# fakealarm.net
KiCad netlist of a schematic drawn in EAGLE
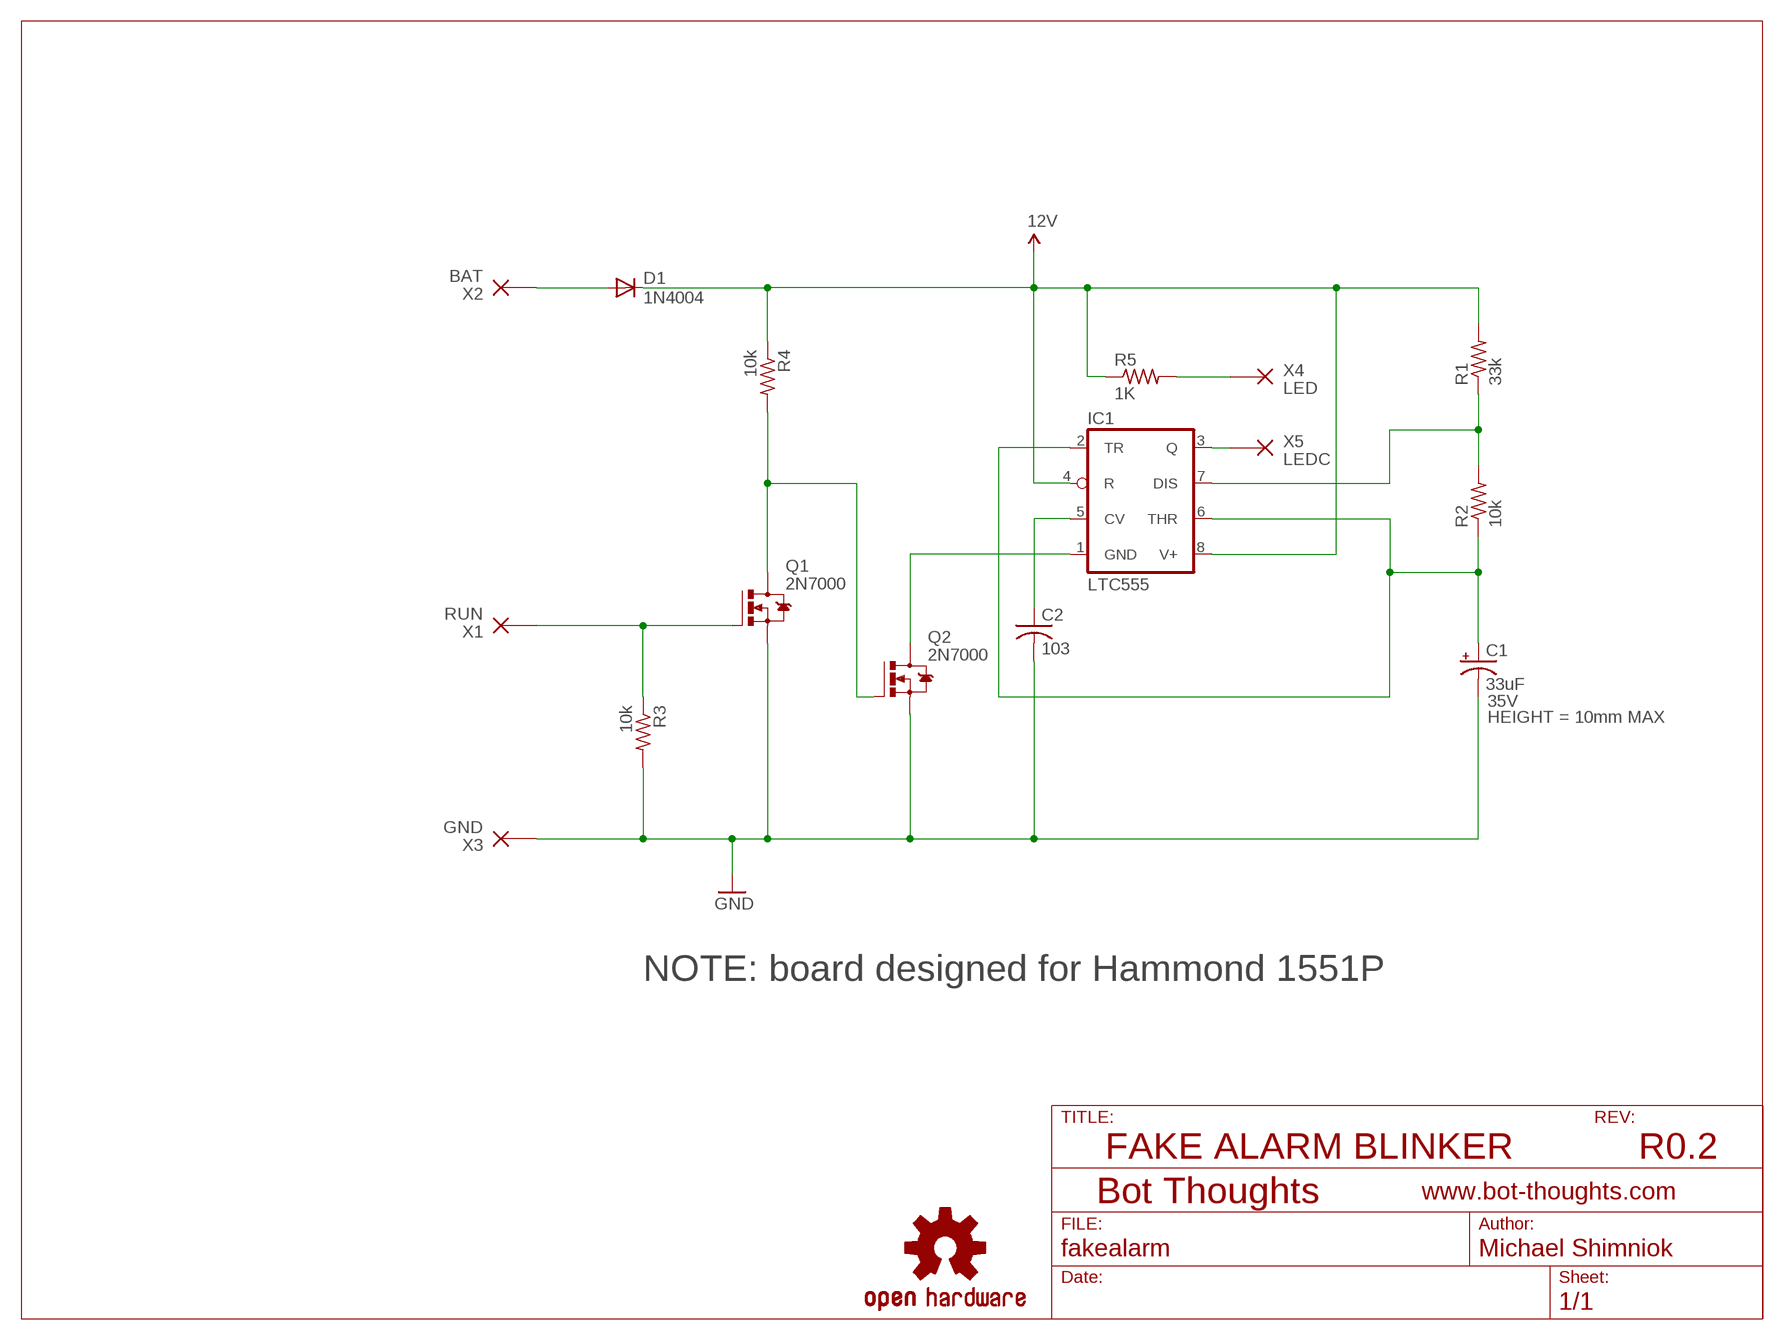
[diagram p0: schematic, sheet 1]

(export (version "E")
  (design (tool "Eeschema 10.0.6"))
  (components
    (comp (ref "C1")
      (value "33uF")
      (footprint "eagle-import:E2,5-6")
      (fields (field (name "HEIGHT") "10mm MAX") (field (name "VOLTAGE") "35V"))
      (libsource (lib "eagle-import") (part "CPOL-USE2.5-6"))
    )
    (comp (ref "C2")
      (value "103")
      (footprint "eagle-import:C050-024X044")
      (libsource (lib "eagle-import") (part "C-US050-024X044"))
    )
    (comp (ref "D1")
      (value "1N4004")
      (footprint "eagle-import:DO41-10")
      (libsource (lib "eagle-import") (part "1N4004"))
    )
    (comp (ref "IC1")
      (value "LTC555")
      (footprint "eagle-import:DIL08")
      (libsource (lib "eagle-import") (part "555NNE"))
    )
    (comp (ref "LOGO1")
      (value "OSHW-LOGOM")
      (footprint "eagle-import:OSHW-LOGO-M")
      (libsource (lib "eagle-import") (part "OSHW-LOGOM"))
    )
    (comp (ref "Q1")
      (value "2N7000")
      (footprint "eagle-import:TO92D-")
      (libsource (lib "eagle-import") (part "MOSFET-NTO92"))
    )
    (comp (ref "Q2")
      (value "2N7000")
      (footprint "eagle-import:TO92D-")
      (libsource (lib "eagle-import") (part "MOSFET-NTO92"))
    )
    (comp (ref "R1")
      (value "33k")
      (footprint "eagle-import:0207_10")
      (libsource (lib "eagle-import") (part "R-US_0207/10"))
    )
    (comp (ref "R2")
      (value "10k")
      (footprint "eagle-import:0207_10")
      (libsource (lib "eagle-import") (part "R-US_0207/10"))
    )
    (comp (ref "R3")
      (value "10k")
      (footprint "eagle-import:0207_10")
      (libsource (lib "eagle-import") (part "R-US_0207/10"))
    )
    (comp (ref "R4")
      (value "10k")
      (footprint "eagle-import:0207_10")
      (libsource (lib "eagle-import") (part "R-US_0207/10"))
    )
    (comp (ref "R5")
      (value "1K")
      (footprint "eagle-import:0207_10")
      (libsource (lib "eagle-import") (part "R-US_0207/10"))
    )
    (comp (ref "X1")
      (value "RUN")
      (footprint "eagle-import:PAD_14GA")
      (libsource (lib "eagle-import") (part "WIREPAD_14GA"))
    )
    (comp (ref "X2")
      (value "BAT")
      (footprint "eagle-import:PAD_14GA")
      (libsource (lib "eagle-import") (part "WIREPAD_14GA"))
    )
    (comp (ref "X3")
      (value "GND")
      (footprint "eagle-import:PAD_14GA")
      (libsource (lib "eagle-import") (part "WIREPAD_14GA"))
    )
    (comp (ref "X4")
      (value "LED")
      (footprint "eagle-import:PAD_24GA")
      (libsource (lib "eagle-import") (part "WIREPAD_24GA"))
    )
    (comp (ref "X5")
      (value "LEDC")
      (footprint "eagle-import:PAD_24GA")
      (libsource (lib "eagle-import") (part "WIREPAD_24GA"))
    )
  )
  (nets
    (net (code "1") (name "12V") (class "Default")
      (node (ref "D1") (pin "C") (pinfunction "C_C") (pintype "passive"))
      (node (ref "IC1") (pin "4") (pinfunction "R_4") (pintype "input"))
      (node (ref "IC1") (pin "8") (pinfunction "V+_8") (pintype "power_in"))
      (node (ref "R1") (pin "2") (pinfunction "2_2") (pintype "passive"))
      (node (ref "R4") (pin "1") (pinfunction "1_1") (pintype "passive"))
      (node (ref "R5") (pin "1") (pinfunction "1_1") (pintype "passive"))
    )
    (net (code "2") (name "GND") (class "Default")
      (node (ref "C1") (pin "-") (pinfunction "-_-") (pintype "passive"))
      (node (ref "C2") (pin "2") (pinfunction "2_2") (pintype "passive"))
      (node (ref "Q1") (pin "1") (pinfunction "S_1") (pintype "passive"))
      (node (ref "Q2") (pin "1") (pinfunction "S_1") (pintype "passive"))
      (node (ref "R3") (pin "2") (pinfunction "2_2") (pintype "passive"))
      (node (ref "X3") (pin "P$1") (pinfunction "P_P$1") (pintype "bidirectional"))
    )
    (net (code "3") (name "Net-(IC1-CV)") (class "Default")
      (node (ref "C2") (pin "1") (pinfunction "1_1") (pintype "passive"))
      (node (ref "IC1") (pin "5") (pinfunction "CV_5") (pintype "input"))
    )
    (net (code "4") (name "Net-(IC1-DIS)") (class "Default")
      (node (ref "IC1") (pin "7") (pinfunction "DIS_7") (pintype "input"))
      (node (ref "R1") (pin "1") (pinfunction "1_1") (pintype "passive"))
      (node (ref "R2") (pin "2") (pinfunction "2_2") (pintype "passive"))
    )
    (net (code "5") (name "Net-(IC1-GND)") (class "Default")
      (node (ref "IC1") (pin "1") (pinfunction "GND_1") (pintype "power_in"))
      (node (ref "Q2") (pin "3") (pinfunction "D_3") (pintype "passive"))
    )
    (net (code "6") (name "Net-(IC1-Q)") (class "Default")
      (node (ref "IC1") (pin "3") (pinfunction "Q_3") (pintype "output"))
      (node (ref "X5") (pin "P$1") (pinfunction "P_P$1") (pintype "bidirectional"))
    )
    (net (code "7") (name "Net-(IC1-THR)") (class "Default")
      (node (ref "C1") (pin "+") (pinfunction "+_+") (pintype "passive"))
      (node (ref "IC1") (pin "2") (pinfunction "TR_2") (pintype "input"))
      (node (ref "IC1") (pin "6") (pinfunction "THR_6") (pintype "input"))
      (node (ref "R2") (pin "1") (pinfunction "1_1") (pintype "passive"))
    )
    (net (code "8") (name "Net-(Q1-D)") (class "Default")
      (node (ref "Q1") (pin "3") (pinfunction "D_3") (pintype "passive"))
      (node (ref "Q2") (pin "2") (pinfunction "G_2") (pintype "passive"))
      (node (ref "R4") (pin "2") (pinfunction "2_2") (pintype "passive"))
    )
    (net (code "9") (name "Net-(Q1-G)") (class "Default")
      (node (ref "Q1") (pin "2") (pinfunction "G_2") (pintype "passive"))
      (node (ref "R3") (pin "1") (pinfunction "1_1") (pintype "passive"))
      (node (ref "X1") (pin "P$1") (pinfunction "P_P$1") (pintype "bidirectional"))
    )
    (net (code "10") (name "Net-(X2-P)") (class "Default")
      (node (ref "D1") (pin "A") (pinfunction "A_A") (pintype "passive"))
      (node (ref "X2") (pin "P$1") (pinfunction "P_P$1") (pintype "bidirectional"))
    )
    (net (code "11") (name "Net-(X4-P)") (class "Default")
      (node (ref "R5") (pin "2") (pinfunction "2_2") (pintype "passive"))
      (node (ref "X4") (pin "P$1") (pinfunction "P_P$1") (pintype "bidirectional"))
    )
  )
)
